# 8-PORT.net
KiCad netlist of a schematic drawn in Altium Designer
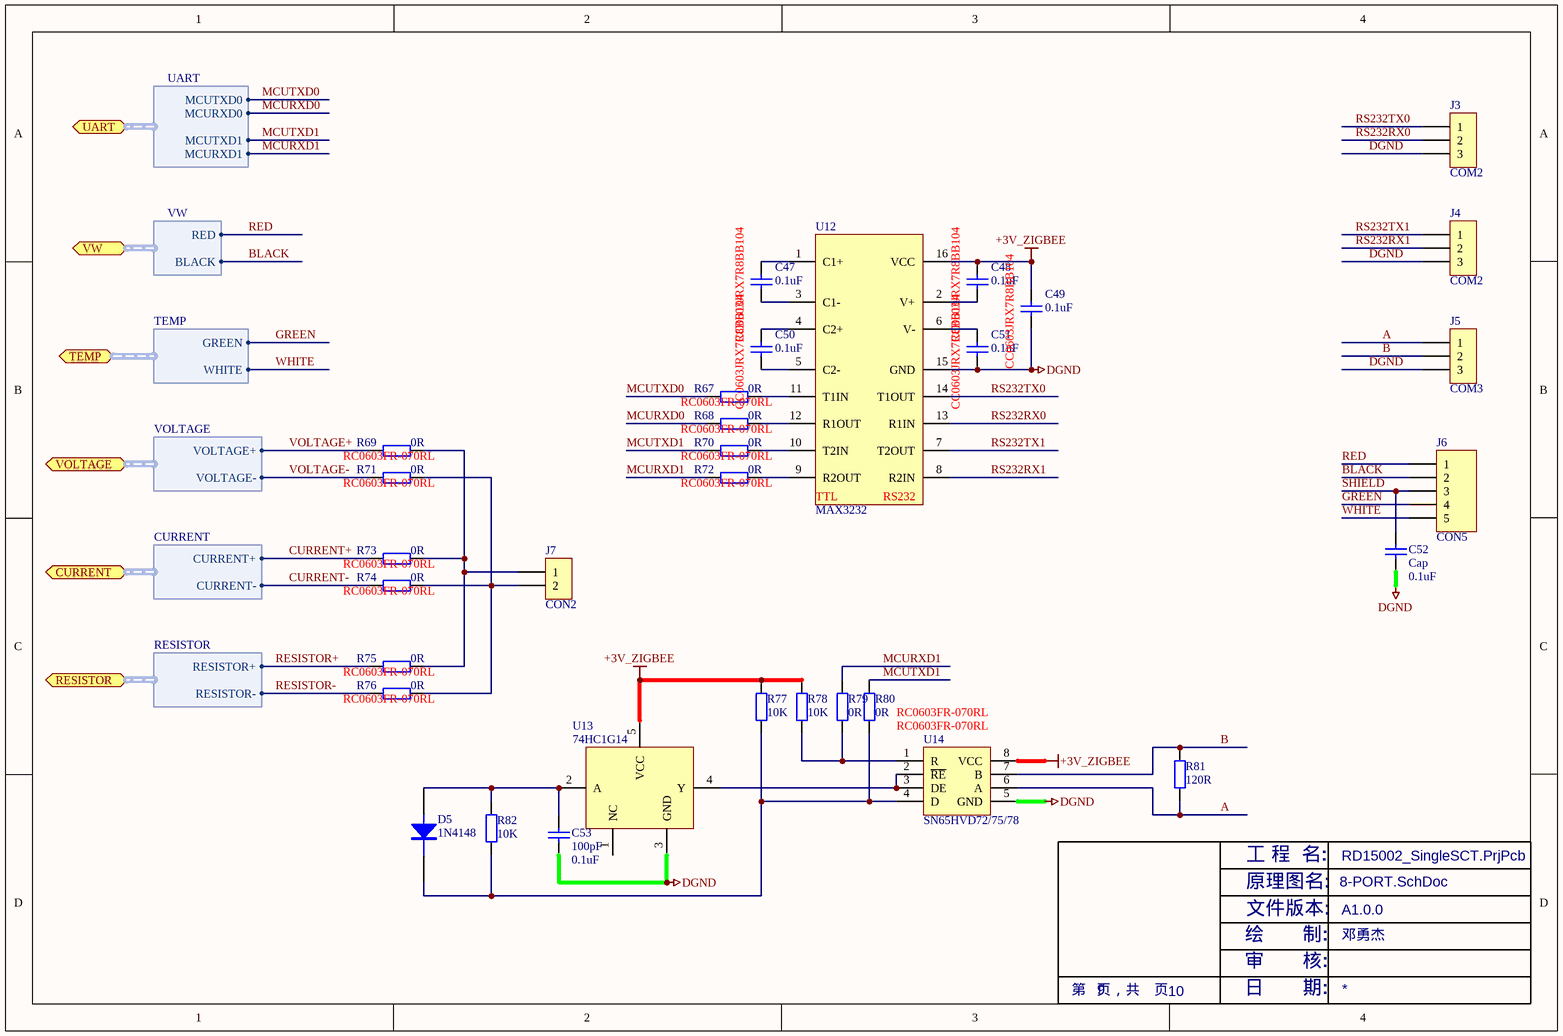
[diagram p0: 8-PORT.SchDoc]

(export (version "E")
  (design (tool "Eeschema 10.0.6"))
  (components
    (comp (ref "C47")
      (value "0.1uF")
      (footprint "CC0603")
      (description "Capacitor")
      (fields (field (name "TYPE NO.") "CC0603JRX7R8BB104"))
      (libsource (lib "Miscellaneous Devices") (part "Cap"))
    )
    (comp (ref "C48")
      (value "0.1uF")
      (footprint "CC0603")
      (description "Capacitor")
      (fields (field (name "TYPE NO.") "CC0603JRX7R8BB104"))
      (libsource (lib "Miscellaneous Devices") (part "Cap"))
    )
    (comp (ref "C49")
      (value "0.1uF")
      (footprint "CC0603")
      (description "Capacitor")
      (fields (field (name "TYPE NO.") "CC0603JRX7R8BB104"))
      (libsource (lib "Miscellaneous Devices") (part "Cap"))
    )
    (comp (ref "C50")
      (value "0.1uF")
      (footprint "CC0603")
      (description "Capacitor")
      (fields (field (name "TYPE NO.") "CC0603JRX7R8BB104"))
      (libsource (lib "Miscellaneous Devices") (part "Cap"))
    )
    (comp (ref "C51")
      (value "0.1uF")
      (footprint "CC0603")
      (description "Capacitor")
      (fields (field (name "TYPE NO.") "CC0603JRX7R8BB104"))
      (libsource (lib "Miscellaneous Devices") (part "Cap"))
    )
    (comp (ref "C52")
      (value "Cap")
      (footprint "CC0603")
      (description "Capacitor")
      (fields (field (name "ALTIUM_VALUE") "0.1uF") (field (name "PUBLISHER") "Altium Limited"))
      (libsource (lib "Miscellaneous Devices") (part "Cap"))
    )
    (comp (ref "C53")
      (value "100pF")
      (footprint "CC0603")
      (description "Capacitor")
      (fields (field (name "ALTIUM_VALUE") "0.1uF") (field (name "PUBLISHER") "Altium Limited"))
      (libsource (lib "Miscellaneous Devices") (part "Cap"))
    )
    (comp (ref "D5") (value "1N4148") (footprint "SOD323") (libsource (lib "woylib2015") (part "DIODE")))
    (comp (ref "J3")
      (value "COM2")
      (footprint "ECH350H-3P")
      (description "jointbar")
      (libsource (lib "AD9_WOY") (part "SIP3"))
    )
    (comp (ref "J4")
      (value "COM2")
      (footprint "ECH350H-3P")
      (description "jointbar")
      (libsource (lib "AD9_WOY") (part "SIP3"))
    )
    (comp (ref "J5")
      (value "COM3")
      (footprint "ECH350H-3P")
      (description "jointbar")
      (libsource (lib "AD9_WOY") (part "SIP3"))
    )
    (comp (ref "J6")
      (value "CON5")
      (footprint "ECH350H-5P")
      (description "Header, 5-Pin")
      (fields (field (name "PUBLISHER") "Altium Limited"))
      (libsource (lib "Miscellaneous Connectors") (part "Header 5"))
    )
    (comp (ref "J7")
      (value "CON2")
      (footprint "ECH350H-2P")
      (description "jointbar")
      (libsource (lib "AD9_WOY") (part "SIP2"))
    )
    (comp (ref "R67")
      (value "0R")
      (footprint "CC0603")
      (description "Resistor")
      (fields (field (name "TYPE NO.") "RC0603FR-070RL"))
      (libsource (lib "Miscellaneous Devices") (part "Res2"))
    )
    (comp (ref "R68")
      (value "0R")
      (footprint "CC0603")
      (description "Resistor")
      (fields (field (name "TYPE NO.") "RC0603FR-070RL"))
      (libsource (lib "Miscellaneous Devices") (part "Res2"))
    )
    (comp (ref "R69")
      (value "0R")
      (footprint "CC0603")
      (description "Resistor")
      (fields (field (name "TYPE NO.") "RC0603FR-070RL"))
      (libsource (lib "Miscellaneous Devices") (part "Res2"))
    )
    (comp (ref "R70")
      (value "0R")
      (footprint "CC0603")
      (description "Resistor")
      (fields (field (name "TYPE NO.") "RC0603FR-070RL"))
      (libsource (lib "Miscellaneous Devices") (part "Res2"))
    )
    (comp (ref "R71")
      (value "0R")
      (footprint "CC0603")
      (description "Resistor")
      (fields (field (name "TYPE NO.") "RC0603FR-070RL"))
      (libsource (lib "Miscellaneous Devices") (part "Res2"))
    )
    (comp (ref "R72")
      (value "0R")
      (footprint "CC0603")
      (description "Resistor")
      (fields (field (name "TYPE NO.") "RC0603FR-070RL"))
      (libsource (lib "Miscellaneous Devices") (part "Res2"))
    )
    (comp (ref "R73")
      (value "0R")
      (footprint "CC0603")
      (description "Resistor")
      (fields (field (name "TYPE NO.") "RC0603FR-070RL"))
      (libsource (lib "Miscellaneous Devices") (part "Res2"))
    )
    (comp (ref "R74")
      (value "0R")
      (footprint "CC0603")
      (description "Resistor")
      (fields (field (name "TYPE NO.") "RC0603FR-070RL"))
      (libsource (lib "Miscellaneous Devices") (part "Res2"))
    )
    (comp (ref "R75")
      (value "0R")
      (footprint "CC0603")
      (description "Resistor")
      (fields (field (name "TYPE NO.") "RC0603FR-070RL"))
      (libsource (lib "Miscellaneous Devices") (part "Res2"))
    )
    (comp (ref "R76")
      (value "0R")
      (footprint "CC0603")
      (description "Resistor")
      (fields (field (name "TYPE NO.") "RC0603FR-070RL"))
      (libsource (lib "Miscellaneous Devices") (part "Res2"))
    )
    (comp (ref "R77")
      (value "10K")
      (footprint "CC0603")
      (description "Resistor")
      (fields (field (name "PUBLISHER") "Altium Limited"))
      (libsource (lib "") (part "Res2_1"))
    )
    (comp (ref "R78")
      (value "10K")
      (footprint "CC0603")
      (description "Resistor")
      (fields (field (name "PUBLISHER") "Altium Limited"))
      (libsource (lib "") (part "Res2_2"))
    )
    (comp (ref "R79")
      (value "0R")
      (footprint "CC0603")
      (description "Resistor")
      (fields (field (name "TYPE NO.") "RC0603FR-070RL"))
      (libsource (lib "") (part "Res2_2"))
    )
    (comp (ref "R80")
      (value "0R")
      (footprint "CC0603")
      (description "Resistor")
      (fields (field (name "TYPE NO.") "RC0603FR-070RL"))
      (libsource (lib "") (part "Res2_2"))
    )
    (comp (ref "R81")
      (value "120R")
      (footprint "CC0603")
      (description "Resistor")
      (fields (field (name "PUBLISHER") "Altium Limited"))
      (libsource (lib "") (part "Res2_1"))
    )
    (comp (ref "R82")
      (value "10K")
      (footprint "CC0603")
      (description "Resistor")
      (fields (field (name "PUBLISHER") "Altium Limited"))
      (libsource (lib "") (part "Res2_1"))
    )
    (comp (ref "U12")
      (value "MAX3232")
      (footprint "SO-16")
      (description "communication  IC")
      (libsource (lib "IC") (part "MAX3232"))
    )
    (comp (ref "U13")
      (value "74HC1G14")
      (footprint "SOT-23-5")
      (libsource (lib "woylib2015") (part "74HC1G14"))
    )
    (comp (ref "U14")
      (value "SN65HVD72/75/78")
      (footprint "SO-8")
      (libsource (lib "IC") (part "SN65HVD72/75/78"))
    )
  )
  (nets
    (net (code "7") (name "+3V_ZIGBEE") (class "Default")
      (node (ref "C48") (pin "2") (pinfunction "2_2") (pintype "passive"))
      (node (ref "C49") (pin "2") (pinfunction "2_2") (pintype "passive"))
      (node (ref "R77") (pin "2") (pinfunction "2_2") (pintype "passive"))
      (node (ref "R78") (pin "1") (pinfunction "1_1") (pintype "passive"))
      (node (ref "U12") (pin "16") (pinfunction "VCC_16") (pintype "power_in"))
      (node (ref "U13") (pin "5") (pinfunction "VCC_5") (pintype "passive"))
      (node (ref "U14") (pin "8") (pinfunction "VCC_8") (pintype "passive"))
    )
    (net (code "8") (name "/A") (class "Default")
      (node (ref "J5") (pin "1") (pinfunction "1_1") (pintype "passive"))
      (node (ref "R81") (pin "1") (pinfunction "1_1") (pintype "passive"))
      (node (ref "U14") (pin "6") (pinfunction "A_6") (pintype "passive"))
    )
    (net (code "9") (name "/B") (class "Default")
      (node (ref "J5") (pin "2") (pinfunction "2_2") (pintype "passive"))
      (node (ref "R81") (pin "2") (pinfunction "2_2") (pintype "passive"))
      (node (ref "U14") (pin "7") (pinfunction "B_7") (pintype "passive"))
    )
    (net (code "10") (name "/BLACK") (class "Default")
      (node (ref "J6") (pin "2") (pinfunction "2_2") (pintype "passive"))
    )
    (net (code "11") (name "/CURRENT+") (class "Default")
      (node (ref "R73") (pin "2") (pinfunction "2_2") (pintype "passive"))
    )
    (net (code "12") (name "/CURRENT-") (class "Default")
      (node (ref "R74") (pin "2") (pinfunction "2_2") (pintype "passive"))
    )
    (net (code "13") (name "/GREEN") (class "Default")
      (node (ref "J6") (pin "4") (pinfunction "4_4") (pintype "passive"))
    )
    (net (code "14") (name "/MCURXD0") (class "Default")
      (node (ref "R68") (pin "2") (pinfunction "2_2") (pintype "passive"))
    )
    (net (code "15") (name "/MCURXD1") (class "Default")
      (node (ref "R72") (pin "2") (pinfunction "2_2") (pintype "passive"))
      (node (ref "R79") (pin "1") (pinfunction "1_1") (pintype "passive"))
    )
    (net (code "16") (name "/MCUTXD0") (class "Default")
      (node (ref "R67") (pin "2") (pinfunction "2_2") (pintype "passive"))
    )
    (net (code "17") (name "/MCUTXD1") (class "Default")
      (node (ref "R70") (pin "2") (pinfunction "2_2") (pintype "passive"))
      (node (ref "R80") (pin "1") (pinfunction "1_1") (pintype "passive"))
    )
    (net (code "18") (name "/RED") (class "Default")
      (node (ref "J6") (pin "1") (pinfunction "1_1") (pintype "passive"))
    )
    (net (code "19") (name "/RESISTOR+") (class "Default")
      (node (ref "R75") (pin "2") (pinfunction "2_2") (pintype "passive"))
    )
    (net (code "20") (name "/RESISTOR-") (class "Default")
      (node (ref "R76") (pin "2") (pinfunction "2_2") (pintype "passive"))
    )
    (net (code "21") (name "/RS232RX0") (class "Default")
      (node (ref "J3") (pin "2") (pinfunction "2_2") (pintype "passive"))
      (node (ref "U12") (pin "13") (pinfunction "R1IN_13") (pintype "passive"))
    )
    (net (code "22") (name "/RS232RX1") (class "Default")
      (node (ref "J4") (pin "2") (pinfunction "2_2") (pintype "passive"))
      (node (ref "U12") (pin "8") (pinfunction "R2IN_8") (pintype "passive"))
    )
    (net (code "23") (name "/RS232TX0") (class "Default")
      (node (ref "J3") (pin "1") (pinfunction "1_1") (pintype "passive"))
      (node (ref "U12") (pin "14") (pinfunction "T1OUT_14") (pintype "passive"))
    )
    (net (code "24") (name "/RS232TX1") (class "Default")
      (node (ref "J4") (pin "1") (pinfunction "1_1") (pintype "passive"))
      (node (ref "U12") (pin "7") (pinfunction "T2OUT_7") (pintype "passive"))
    )
    (net (code "25") (name "/SHIELD") (class "Default")
      (node (ref "C52") (pin "2") (pinfunction "2_2") (pintype "passive"))
      (node (ref "J6") (pin "3") (pinfunction "3_3") (pintype "passive"))
    )
    (net (code "26") (name "/VOLTAGE+") (class "Default")
      (node (ref "R69") (pin "2") (pinfunction "2_2") (pintype "passive"))
    )
    (net (code "27") (name "/VOLTAGE-") (class "Default")
      (node (ref "R71") (pin "2") (pinfunction "2_2") (pintype "passive"))
    )
    (net (code "28") (name "/WHITE") (class "Default")
      (node (ref "J6") (pin "5") (pinfunction "5_5") (pintype "passive"))
    )
    (net (code "35") (name "DGND") (class "Default")
      (node (ref "C49") (pin "1") (pinfunction "1_1") (pintype "passive"))
      (node (ref "C51") (pin "1") (pinfunction "1_1") (pintype "passive"))
      (node (ref "C52") (pin "1") (pinfunction "1_1") (pintype "passive"))
      (node (ref "C53") (pin "1") (pinfunction "1_1") (pintype "passive"))
      (node (ref "J3") (pin "3") (pinfunction "3_3") (pintype "passive"))
      (node (ref "J4") (pin "3") (pinfunction "3_3") (pintype "passive"))
      (node (ref "J5") (pin "3") (pinfunction "3_3") (pintype "passive"))
      (node (ref "U12") (pin "15") (pinfunction "GND_15") (pintype "power_in"))
      (node (ref "U13") (pin "3") (pinfunction "GND_3") (pintype "passive"))
      (node (ref "U14") (pin "5") (pinfunction "GND_5") (pintype "passive"))
    )
    (net (code "36") (name "Net-(D5-A)") (class "Default")
      (node (ref "C53") (pin "2") (pinfunction "2_2") (pintype "passive"))
      (node (ref "D5") (pin "1") (pinfunction "A_1") (pintype "passive"))
      (node (ref "R82") (pin "2") (pinfunction "2_2") (pintype "passive"))
      (node (ref "U13") (pin "2") (pinfunction "A_2") (pintype "passive"))
    )
    (net (code "37") (name "Net-(D5-K)") (class "Default")
      (node (ref "D5") (pin "2") (pinfunction "K_2") (pintype "passive"))
      (node (ref "R77") (pin "1") (pinfunction "1_1") (pintype "passive"))
      (node (ref "R80") (pin "2") (pinfunction "2_2") (pintype "passive"))
      (node (ref "R82") (pin "1") (pinfunction "1_1") (pintype "passive"))
      (node (ref "U14") (pin "4") (pinfunction "D_4") (pintype "passive"))
    )
    (net (code "38") (name "Net-(J7-Pad1)") (class "Default")
      (node (ref "J7") (pin "1") (pinfunction "1_1") (pintype "passive"))
      (node (ref "R69") (pin "1") (pinfunction "1_1") (pintype "passive"))
      (node (ref "R73") (pin "1") (pinfunction "1_1") (pintype "passive"))
      (node (ref "R75") (pin "1") (pinfunction "1_1") (pintype "passive"))
    )
    (net (code "39") (name "Net-(J7-Pad2)") (class "Default")
      (node (ref "J7") (pin "2") (pinfunction "2_2") (pintype "passive"))
      (node (ref "R71") (pin "1") (pinfunction "1_1") (pintype "passive"))
      (node (ref "R74") (pin "1") (pinfunction "1_1") (pintype "passive"))
      (node (ref "R76") (pin "1") (pinfunction "1_1") (pintype "passive"))
    )
    (net (code "40") (name "Net-(U12-C1+)") (class "Default")
      (node (ref "C47") (pin "2") (pinfunction "2_2") (pintype "passive"))
      (node (ref "U12") (pin "1") (pinfunction "C1+_1") (pintype "passive"))
    )
    (net (code "41") (name "Net-(U12-C1-)") (class "Default")
      (node (ref "C47") (pin "1") (pinfunction "1_1") (pintype "passive"))
      (node (ref "U12") (pin "3") (pinfunction "C1-_3") (pintype "passive"))
    )
    (net (code "42") (name "Net-(U12-C2+)") (class "Default")
      (node (ref "C50") (pin "2") (pinfunction "2_2") (pintype "passive"))
      (node (ref "U12") (pin "4") (pinfunction "C2+_4") (pintype "passive"))
    )
    (net (code "43") (name "Net-(U12-C2-)") (class "Default")
      (node (ref "C50") (pin "1") (pinfunction "1_1") (pintype "passive"))
      (node (ref "U12") (pin "5") (pinfunction "C2-_5") (pintype "passive"))
    )
    (net (code "44") (name "Net-(U12-R1OUT)") (class "Default")
      (node (ref "R68") (pin "1") (pinfunction "1_1") (pintype "passive"))
      (node (ref "U12") (pin "12") (pinfunction "R1OUT_12") (pintype "passive"))
    )
    (net (code "45") (name "Net-(U12-R2OUT)") (class "Default")
      (node (ref "R72") (pin "1") (pinfunction "1_1") (pintype "passive"))
      (node (ref "U12") (pin "9") (pinfunction "R2OUT_9") (pintype "passive"))
    )
    (net (code "46") (name "Net-(U12-T1IN)") (class "Default")
      (node (ref "R67") (pin "1") (pinfunction "1_1") (pintype "passive"))
      (node (ref "U12") (pin "11") (pinfunction "T1IN_11") (pintype "passive"))
    )
    (net (code "47") (name "Net-(U12-T2IN)") (class "Default")
      (node (ref "R70") (pin "1") (pinfunction "1_1") (pintype "passive"))
      (node (ref "U12") (pin "10") (pinfunction "T2IN_10") (pintype "passive"))
    )
    (net (code "48") (name "Net-(U12-V+)") (class "Default")
      (node (ref "C48") (pin "1") (pinfunction "1_1") (pintype "passive"))
      (node (ref "U12") (pin "2") (pinfunction "V+_2") (pintype "passive"))
    )
    (net (code "49") (name "Net-(U12-V-)") (class "Default")
      (node (ref "C51") (pin "2") (pinfunction "2_2") (pintype "passive"))
      (node (ref "U12") (pin "6") (pinfunction "V-_6") (pintype "passive"))
    )
    (net (code "50") (name "Net-(U13-Y)") (class "Default")
      (node (ref "U13") (pin "4") (pinfunction "Y_4") (pintype "passive"))
      (node (ref "U14") (pin "2") (pinfunction "~{RE}_2") (pintype "passive"))
      (node (ref "U14") (pin "3") (pinfunction "DE_3") (pintype "passive"))
    )
    (net (code "51") (name "Net-(U14-R)") (class "Default")
      (node (ref "R78") (pin "2") (pinfunction "2_2") (pintype "passive"))
      (node (ref "R79") (pin "2") (pinfunction "2_2") (pintype "passive"))
      (node (ref "U14") (pin "1") (pinfunction "R_1") (pintype "passive"))
    )
    (net (code "52") (name "unconnected-(U13-NC-Pad1)") (class "Default")
      (node (ref "U13") (pin "1") (pinfunction "NC_1") (pintype "passive"))
    )
  )
)
